# MainBoard.net
KiCad netlist of a schematic drawn in EAGLE
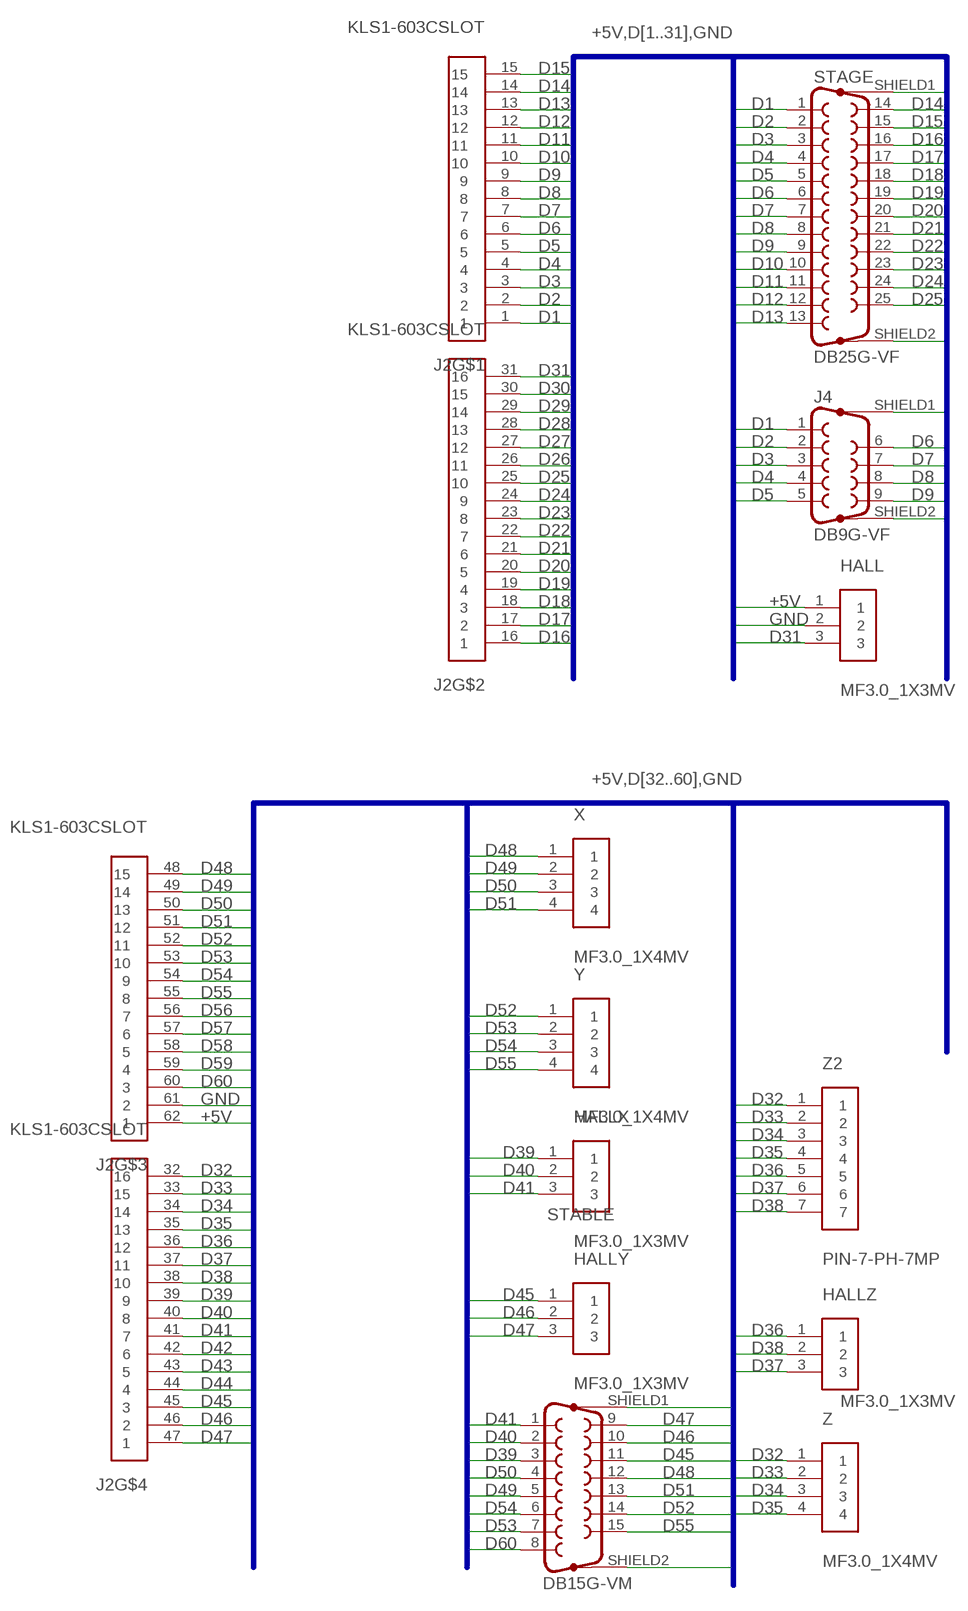
[diagram p0: schematic, sheet 1]

(export (version "E")
  (design (tool "Eeschema 10.0.6"))
  (components
    (comp (ref "HALL")
      (value "MF3.0_1X3MV")
      (footprint "eagle-import:MF3.0_1X3MV")
      (libsource (lib "eagle-import") (part "MF3.0_1X3MV"))
    )
    (comp (ref "HALLX")
      (value "MF3.0_1X3MV")
      (footprint "eagle-import:MF3.0_1X3MV")
      (libsource (lib "eagle-import") (part "MF3.0_1X3MV"))
    )
    (comp (ref "HALLY")
      (value "MF3.0_1X3MV")
      (footprint "eagle-import:MF3.0_1X3MV")
      (libsource (lib "eagle-import") (part "MF3.0_1X3MV"))
    )
    (comp (ref "HALLZ")
      (value "MF3.0_1X3MV")
      (footprint "eagle-import:MF3.0_1X3MV")
      (libsource (lib "eagle-import") (part "MF3.0_1X3MV"))
    )
    (comp (ref "J2")
      (value "KLS1-603CSLOT")
      (footprint "eagle-import:KLS1-603C-SLOT")
      (libsource (lib "eagle-import") (part "KLS1-603CSLOT"))
    )
    (comp (ref "J4")
      (value "DB9G-VF")
      (footprint "eagle-import:DB9G-F")
      (libsource (lib "eagle-import") (part "DB9G-VF"))
    )
    (comp (ref "STABLE")
      (value "DB15G-VM")
      (footprint "eagle-import:DS1034-15")
      (libsource (lib "eagle-import") (part "DB15G-VM"))
    )
    (comp (ref "STAGE")
      (value "DB25G-VF")
      (footprint "eagle-import:DB25G-F")
      (libsource (lib "eagle-import") (part "DB25G-VF"))
    )
    (comp (ref "X")
      (value "MF3.0_1X4MV")
      (footprint "eagle-import:MF3.0_1X4MV")
      (libsource (lib "eagle-import") (part "MF3.0_1X4MV"))
    )
    (comp (ref "Y")
      (value "MF3.0_1X4MV")
      (footprint "eagle-import:MF3.0_1X4MV")
      (libsource (lib "eagle-import") (part "MF3.0_1X4MV"))
    )
    (comp (ref "Z")
      (value "MF3.0_1X4MV")
      (footprint "eagle-import:MF3.0_1X4MV")
      (libsource (lib "eagle-import") (part "MF3.0_1X4MV"))
    )
    (comp (ref "Z2")
      (value "PIN-7-PH-7MP")
      (footprint "eagle-import:PH-7MP")
      (libsource (lib "eagle-import") (part "PIN-7-PH-7MP"))
    )
  )
  (nets
    (net (code "1") (name "/+5V") (class "Default")
      (node (ref "HALL") (pin "1") (pinfunction "1_1") (pintype "bidirectional"))
      (node (ref "J2") (pin "62") (pinfunction "1_62") (pintype "bidirectional"))
    )
    (net (code "2") (name "/D1") (class "Default")
      (node (ref "J2") (pin "1") (pinfunction "1_1") (pintype "bidirectional"))
      (node (ref "J4") (pin "1") (pinfunction "1_1") (pintype "passive"))
      (node (ref "STAGE") (pin "1") (pinfunction "1_1") (pintype "passive"))
    )
    (net (code "3") (name "/D2") (class "Default")
      (node (ref "J2") (pin "2") (pinfunction "2_2") (pintype "bidirectional"))
      (node (ref "J4") (pin "2") (pinfunction "2_2") (pintype "passive"))
      (node (ref "STAGE") (pin "2") (pinfunction "2_2") (pintype "passive"))
    )
    (net (code "4") (name "/D3") (class "Default")
      (node (ref "J2") (pin "3") (pinfunction "3_3") (pintype "bidirectional"))
      (node (ref "J4") (pin "3") (pinfunction "3_3") (pintype "passive"))
      (node (ref "STAGE") (pin "3") (pinfunction "3_3") (pintype "passive"))
    )
    (net (code "5") (name "/D4") (class "Default")
      (node (ref "J2") (pin "4") (pinfunction "4_4") (pintype "bidirectional"))
      (node (ref "J4") (pin "4") (pinfunction "4_4") (pintype "passive"))
      (node (ref "STAGE") (pin "4") (pinfunction "4_4") (pintype "passive"))
    )
    (net (code "6") (name "/D5") (class "Default")
      (node (ref "J2") (pin "5") (pinfunction "5_5") (pintype "bidirectional"))
      (node (ref "J4") (pin "5") (pinfunction "5_5") (pintype "passive"))
      (node (ref "STAGE") (pin "5") (pinfunction "5_5") (pintype "passive"))
    )
    (net (code "7") (name "/D6") (class "Default")
      (node (ref "J2") (pin "6") (pinfunction "6_6") (pintype "bidirectional"))
      (node (ref "J4") (pin "6") (pinfunction "6_6") (pintype "passive"))
      (node (ref "STAGE") (pin "6") (pinfunction "6_6") (pintype "passive"))
    )
    (net (code "8") (name "/D7") (class "Default")
      (node (ref "J2") (pin "7") (pinfunction "7_7") (pintype "bidirectional"))
      (node (ref "J4") (pin "7") (pinfunction "7_7") (pintype "passive"))
      (node (ref "STAGE") (pin "7") (pinfunction "7_7") (pintype "passive"))
    )
    (net (code "9") (name "/D8") (class "Default")
      (node (ref "J2") (pin "8") (pinfunction "8_8") (pintype "bidirectional"))
      (node (ref "J4") (pin "8") (pinfunction "8_8") (pintype "passive"))
      (node (ref "STAGE") (pin "8") (pinfunction "8_8") (pintype "passive"))
    )
    (net (code "10") (name "/D9") (class "Default")
      (node (ref "J2") (pin "9") (pinfunction "9_9") (pintype "bidirectional"))
      (node (ref "J4") (pin "9") (pinfunction "9_9") (pintype "passive"))
      (node (ref "STAGE") (pin "9") (pinfunction "9_9") (pintype "passive"))
    )
    (net (code "11") (name "/D10") (class "Default")
      (node (ref "J2") (pin "10") (pinfunction "10_10") (pintype "bidirectional"))
      (node (ref "STAGE") (pin "10") (pinfunction "10_10") (pintype "passive"))
    )
    (net (code "12") (name "/D11") (class "Default")
      (node (ref "J2") (pin "11") (pinfunction "11_11") (pintype "bidirectional"))
      (node (ref "STAGE") (pin "11") (pinfunction "11_11") (pintype "passive"))
    )
    (net (code "13") (name "/D12") (class "Default")
      (node (ref "J2") (pin "12") (pinfunction "12_12") (pintype "bidirectional"))
      (node (ref "STAGE") (pin "12") (pinfunction "12_12") (pintype "passive"))
    )
    (net (code "14") (name "/D13") (class "Default")
      (node (ref "J2") (pin "13") (pinfunction "13_13") (pintype "bidirectional"))
      (node (ref "STAGE") (pin "13") (pinfunction "13_13") (pintype "passive"))
    )
    (net (code "15") (name "/D14") (class "Default")
      (node (ref "J2") (pin "14") (pinfunction "14_14") (pintype "bidirectional"))
      (node (ref "STAGE") (pin "14") (pinfunction "14_14") (pintype "passive"))
    )
    (net (code "16") (name "/D15") (class "Default")
      (node (ref "J2") (pin "15") (pinfunction "15_15") (pintype "bidirectional"))
      (node (ref "STAGE") (pin "15") (pinfunction "15_15") (pintype "passive"))
    )
    (net (code "17") (name "/D16") (class "Default")
      (node (ref "J2") (pin "16") (pinfunction "1_16") (pintype "bidirectional"))
      (node (ref "STAGE") (pin "16") (pinfunction "16_16") (pintype "passive"))
    )
    (net (code "18") (name "/D17") (class "Default")
      (node (ref "J2") (pin "17") (pinfunction "2_17") (pintype "bidirectional"))
      (node (ref "STAGE") (pin "17") (pinfunction "17_17") (pintype "passive"))
    )
    (net (code "19") (name "/D18") (class "Default")
      (node (ref "J2") (pin "18") (pinfunction "3_18") (pintype "bidirectional"))
      (node (ref "STAGE") (pin "18") (pinfunction "18_18") (pintype "passive"))
    )
    (net (code "20") (name "/D19") (class "Default")
      (node (ref "J2") (pin "19") (pinfunction "4_19") (pintype "bidirectional"))
      (node (ref "STAGE") (pin "19") (pinfunction "19_19") (pintype "passive"))
    )
    (net (code "21") (name "/D20") (class "Default")
      (node (ref "J2") (pin "20") (pinfunction "5_20") (pintype "bidirectional"))
      (node (ref "STAGE") (pin "20") (pinfunction "20_20") (pintype "passive"))
    )
    (net (code "22") (name "/D21") (class "Default")
      (node (ref "J2") (pin "21") (pinfunction "6_21") (pintype "bidirectional"))
      (node (ref "STAGE") (pin "21") (pinfunction "21_21") (pintype "passive"))
    )
    (net (code "23") (name "/D22") (class "Default")
      (node (ref "J2") (pin "22") (pinfunction "7_22") (pintype "bidirectional"))
      (node (ref "STAGE") (pin "22") (pinfunction "22_22") (pintype "passive"))
    )
    (net (code "24") (name "/D23") (class "Default")
      (node (ref "J2") (pin "23") (pinfunction "8_23") (pintype "bidirectional"))
      (node (ref "STAGE") (pin "23") (pinfunction "23_23") (pintype "passive"))
    )
    (net (code "25") (name "/D24") (class "Default")
      (node (ref "J2") (pin "24") (pinfunction "9_24") (pintype "bidirectional"))
      (node (ref "STAGE") (pin "24") (pinfunction "24_24") (pintype "passive"))
    )
    (net (code "26") (name "/D25") (class "Default")
      (node (ref "J2") (pin "25") (pinfunction "10_25") (pintype "bidirectional"))
      (node (ref "STAGE") (pin "25") (pinfunction "25_25") (pintype "passive"))
    )
    (net (code "27") (name "/D26") (class "Default")
      (node (ref "J2") (pin "26") (pinfunction "11_26") (pintype "bidirectional"))
    )
    (net (code "28") (name "/D27") (class "Default")
      (node (ref "J2") (pin "27") (pinfunction "12_27") (pintype "bidirectional"))
    )
    (net (code "29") (name "/D28") (class "Default")
      (node (ref "J2") (pin "28") (pinfunction "13_28") (pintype "bidirectional"))
    )
    (net (code "30") (name "/D29") (class "Default")
      (node (ref "J2") (pin "29") (pinfunction "14_29") (pintype "bidirectional"))
    )
    (net (code "31") (name "/D30") (class "Default")
      (node (ref "J2") (pin "30") (pinfunction "15_30") (pintype "bidirectional"))
    )
    (net (code "32") (name "/D31") (class "Default")
      (node (ref "HALL") (pin "3") (pinfunction "3_3") (pintype "bidirectional"))
      (node (ref "J2") (pin "31") (pinfunction "16_31") (pintype "bidirectional"))
    )
    (net (code "33") (name "/D32") (class "Default")
      (node (ref "J2") (pin "32") (pinfunction "16_32") (pintype "bidirectional"))
      (node (ref "Z") (pin "1") (pinfunction "1_1") (pintype "bidirectional"))
      (node (ref "Z2") (pin "1") (pinfunction "1_1") (pintype "bidirectional"))
    )
    (net (code "34") (name "/D33") (class "Default")
      (node (ref "J2") (pin "33") (pinfunction "15_33") (pintype "bidirectional"))
      (node (ref "Z") (pin "2") (pinfunction "2_2") (pintype "bidirectional"))
      (node (ref "Z2") (pin "2") (pinfunction "2_2") (pintype "bidirectional"))
    )
    (net (code "35") (name "/D34") (class "Default")
      (node (ref "J2") (pin "34") (pinfunction "14_34") (pintype "bidirectional"))
      (node (ref "Z") (pin "3") (pinfunction "3_3") (pintype "bidirectional"))
      (node (ref "Z2") (pin "3") (pinfunction "3_3") (pintype "bidirectional"))
    )
    (net (code "36") (name "/D35") (class "Default")
      (node (ref "J2") (pin "35") (pinfunction "13_35") (pintype "bidirectional"))
      (node (ref "Z") (pin "4") (pinfunction "4_4") (pintype "bidirectional"))
      (node (ref "Z2") (pin "4") (pinfunction "4_4") (pintype "bidirectional"))
    )
    (net (code "37") (name "/D36") (class "Default")
      (node (ref "HALLZ") (pin "1") (pinfunction "1_1") (pintype "bidirectional"))
      (node (ref "J2") (pin "36") (pinfunction "12_36") (pintype "bidirectional"))
      (node (ref "Z2") (pin "5") (pinfunction "5_5") (pintype "bidirectional"))
    )
    (net (code "38") (name "/D37") (class "Default")
      (node (ref "HALLZ") (pin "3") (pinfunction "3_3") (pintype "bidirectional"))
      (node (ref "J2") (pin "37") (pinfunction "11_37") (pintype "bidirectional"))
      (node (ref "Z2") (pin "6") (pinfunction "6_6") (pintype "bidirectional"))
    )
    (net (code "39") (name "/D38") (class "Default")
      (node (ref "HALLZ") (pin "2") (pinfunction "2_2") (pintype "bidirectional"))
      (node (ref "J2") (pin "38") (pinfunction "10_38") (pintype "bidirectional"))
      (node (ref "Z2") (pin "7") (pinfunction "7_7") (pintype "bidirectional"))
    )
    (net (code "40") (name "/D39") (class "Default")
      (node (ref "HALLX") (pin "1") (pinfunction "1_1") (pintype "bidirectional"))
      (node (ref "J2") (pin "39") (pinfunction "9_39") (pintype "bidirectional"))
      (node (ref "STABLE") (pin "3") (pinfunction "3_3") (pintype "passive"))
    )
    (net (code "41") (name "/D40") (class "Default")
      (node (ref "HALLX") (pin "2") (pinfunction "2_2") (pintype "bidirectional"))
      (node (ref "J2") (pin "40") (pinfunction "8_40") (pintype "bidirectional"))
      (node (ref "STABLE") (pin "2") (pinfunction "2_2") (pintype "passive"))
    )
    (net (code "42") (name "/D41") (class "Default")
      (node (ref "HALLX") (pin "3") (pinfunction "3_3") (pintype "bidirectional"))
      (node (ref "J2") (pin "41") (pinfunction "7_41") (pintype "bidirectional"))
      (node (ref "STABLE") (pin "1") (pinfunction "1_1") (pintype "passive"))
    )
    (net (code "43") (name "/D42") (class "Default")
      (node (ref "J2") (pin "42") (pinfunction "6_42") (pintype "bidirectional"))
    )
    (net (code "44") (name "/D43") (class "Default")
      (node (ref "J2") (pin "43") (pinfunction "5_43") (pintype "bidirectional"))
    )
    (net (code "45") (name "/D44") (class "Default")
      (node (ref "J2") (pin "44") (pinfunction "4_44") (pintype "bidirectional"))
    )
    (net (code "46") (name "/D45") (class "Default")
      (node (ref "HALLY") (pin "1") (pinfunction "1_1") (pintype "bidirectional"))
      (node (ref "J2") (pin "45") (pinfunction "3_45") (pintype "bidirectional"))
      (node (ref "STABLE") (pin "11") (pinfunction "11_11") (pintype "passive"))
    )
    (net (code "47") (name "/D46") (class "Default")
      (node (ref "HALLY") (pin "2") (pinfunction "2_2") (pintype "bidirectional"))
      (node (ref "J2") (pin "46") (pinfunction "2_46") (pintype "bidirectional"))
      (node (ref "STABLE") (pin "10") (pinfunction "10_10") (pintype "passive"))
    )
    (net (code "48") (name "/D47") (class "Default")
      (node (ref "HALLY") (pin "3") (pinfunction "3_3") (pintype "bidirectional"))
      (node (ref "J2") (pin "47") (pinfunction "1_47") (pintype "bidirectional"))
      (node (ref "STABLE") (pin "9") (pinfunction "9_9") (pintype "passive"))
    )
    (net (code "49") (name "/D48") (class "Default")
      (node (ref "J2") (pin "48") (pinfunction "15_48") (pintype "bidirectional"))
      (node (ref "STABLE") (pin "12") (pinfunction "12_12") (pintype "passive"))
      (node (ref "X") (pin "1") (pinfunction "1_1") (pintype "bidirectional"))
    )
    (net (code "50") (name "/D49") (class "Default")
      (node (ref "J2") (pin "49") (pinfunction "14_49") (pintype "bidirectional"))
      (node (ref "STABLE") (pin "5") (pinfunction "5_5") (pintype "passive"))
      (node (ref "X") (pin "2") (pinfunction "2_2") (pintype "bidirectional"))
    )
    (net (code "51") (name "/D50") (class "Default")
      (node (ref "J2") (pin "50") (pinfunction "13_50") (pintype "bidirectional"))
      (node (ref "STABLE") (pin "4") (pinfunction "4_4") (pintype "passive"))
      (node (ref "X") (pin "3") (pinfunction "3_3") (pintype "bidirectional"))
    )
    (net (code "52") (name "/D51") (class "Default")
      (node (ref "J2") (pin "51") (pinfunction "12_51") (pintype "bidirectional"))
      (node (ref "STABLE") (pin "13") (pinfunction "13_13") (pintype "passive"))
      (node (ref "X") (pin "4") (pinfunction "4_4") (pintype "bidirectional"))
    )
    (net (code "53") (name "/D52") (class "Default")
      (node (ref "J2") (pin "52") (pinfunction "11_52") (pintype "bidirectional"))
      (node (ref "STABLE") (pin "14") (pinfunction "14_14") (pintype "passive"))
      (node (ref "Y") (pin "1") (pinfunction "1_1") (pintype "bidirectional"))
    )
    (net (code "54") (name "/D53") (class "Default")
      (node (ref "J2") (pin "53") (pinfunction "10_53") (pintype "bidirectional"))
      (node (ref "STABLE") (pin "7") (pinfunction "7_7") (pintype "passive"))
      (node (ref "Y") (pin "2") (pinfunction "2_2") (pintype "bidirectional"))
    )
    (net (code "55") (name "/D54") (class "Default")
      (node (ref "J2") (pin "54") (pinfunction "9_54") (pintype "bidirectional"))
      (node (ref "STABLE") (pin "6") (pinfunction "6_6") (pintype "passive"))
      (node (ref "Y") (pin "3") (pinfunction "3_3") (pintype "bidirectional"))
    )
    (net (code "56") (name "/D55") (class "Default")
      (node (ref "J2") (pin "55") (pinfunction "8_55") (pintype "bidirectional"))
      (node (ref "STABLE") (pin "15") (pinfunction "15_15") (pintype "passive"))
      (node (ref "Y") (pin "4") (pinfunction "4_4") (pintype "bidirectional"))
    )
    (net (code "57") (name "/D56") (class "Default")
      (node (ref "J2") (pin "56") (pinfunction "7_56") (pintype "bidirectional"))
    )
    (net (code "58") (name "/D57") (class "Default")
      (node (ref "J2") (pin "57") (pinfunction "6_57") (pintype "bidirectional"))
    )
    (net (code "59") (name "/D58") (class "Default")
      (node (ref "J2") (pin "58") (pinfunction "5_58") (pintype "bidirectional"))
    )
    (net (code "60") (name "/D59") (class "Default")
      (node (ref "J2") (pin "59") (pinfunction "4_59") (pintype "bidirectional"))
    )
    (net (code "61") (name "/D60") (class "Default")
      (node (ref "J2") (pin "60") (pinfunction "3_60") (pintype "bidirectional"))
      (node (ref "STABLE") (pin "8") (pinfunction "8_8") (pintype "passive"))
    )
    (net (code "62") (name "/GND") (class "Default")
      (node (ref "HALL") (pin "2") (pinfunction "2_2") (pintype "bidirectional"))
      (node (ref "J2") (pin "61") (pinfunction "2_61") (pintype "bidirectional"))
      (node (ref "J4") (pin "SHIELD1") (pinfunction "G1_SHIELD1") (pintype "passive"))
      (node (ref "J4") (pin "SHIELD2") (pinfunction "G2_SHIELD2") (pintype "passive"))
      (node (ref "STABLE") (pin "SHIELD1") (pinfunction "G1_SHIELD1") (pintype "passive"))
      (node (ref "STABLE") (pin "SHIELD2") (pinfunction "G2_SHIELD2") (pintype "passive"))
      (node (ref "STAGE") (pin "SHIELD1") (pinfunction "G1_SHIELD1") (pintype "passive"))
      (node (ref "STAGE") (pin "SHIELD2") (pinfunction "G2_SHIELD2") (pintype "passive"))
    )
  )
)
